# Adafruit_BNO055_and_BMP280_BFF.net
KiCad netlist of a schematic drawn in EAGLE
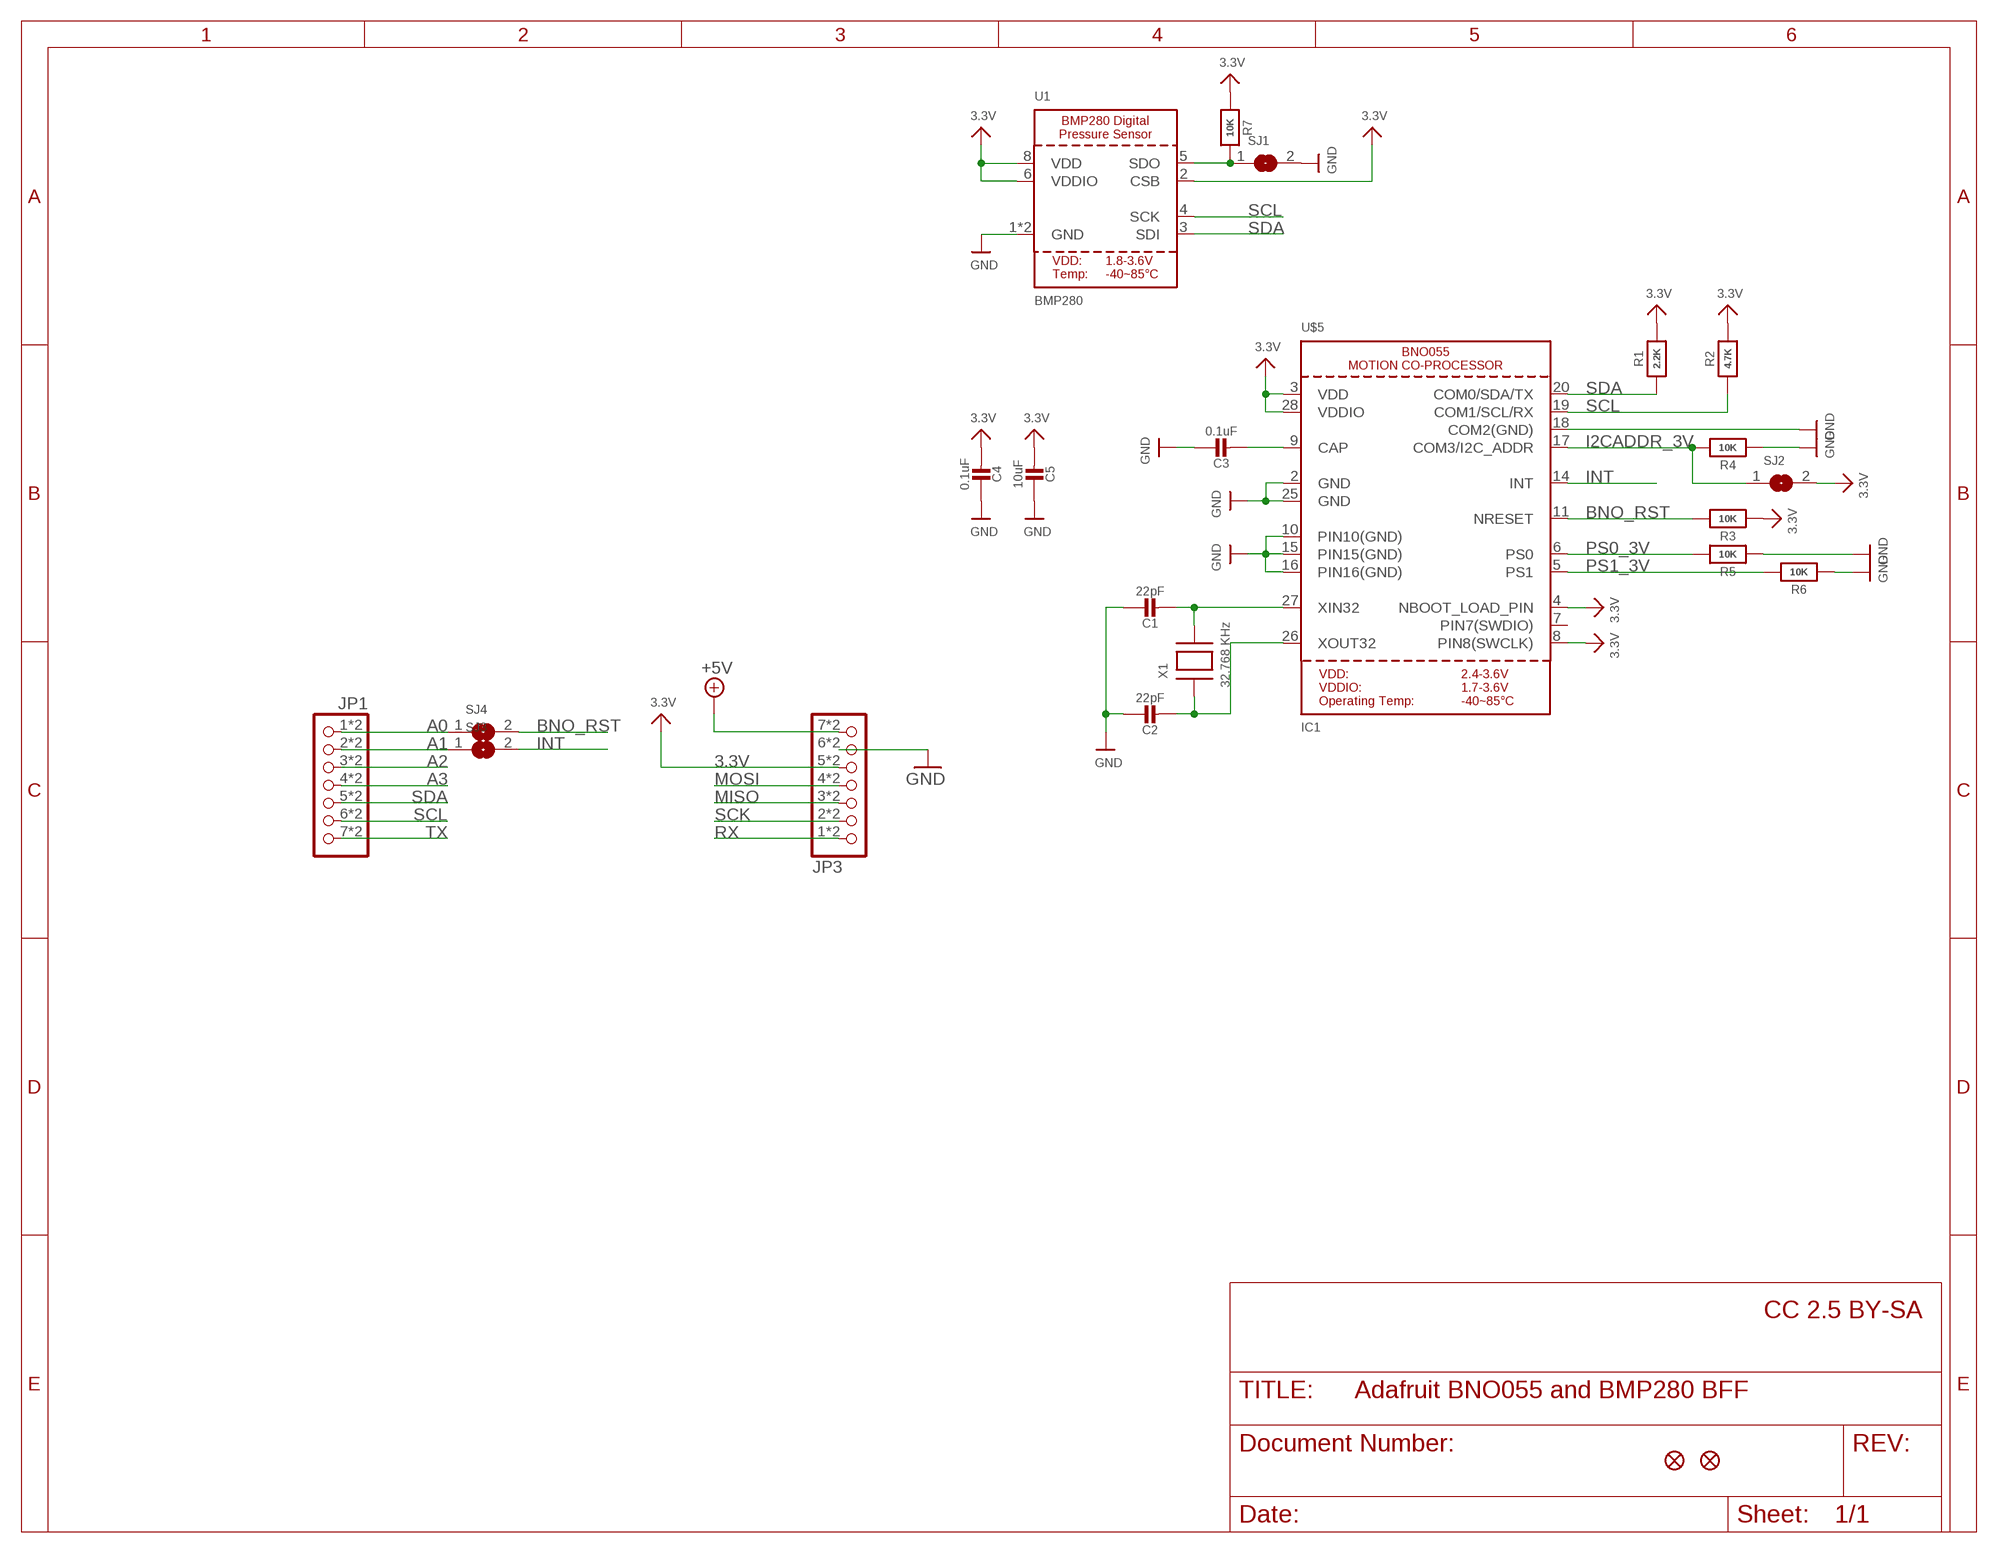
[diagram p0: schematic, sheet 1]

(export (version "E")
  (design (tool "Eeschema 10.0.6"))
  (components
    (comp (ref "C1")
      (value "22pF")
      (footprint "eagle-import:0603-NO")
      (libsource (lib "eagle-import") (part "CAP_CERAMIC0603_NO"))
    )
    (comp (ref "C2")
      (value "22pF")
      (footprint "eagle-import:0603-NO")
      (libsource (lib "eagle-import") (part "CAP_CERAMIC0603_NO"))
    )
    (comp (ref "C3")
      (value "0.1uF")
      (footprint "eagle-import:0603-NO")
      (libsource (lib "eagle-import") (part "CAP_CERAMIC0603_NO"))
    )
    (comp (ref "C4")
      (value "0.1uF")
      (footprint "eagle-import:0603-NO")
      (libsource (lib "eagle-import") (part "CAP_CERAMIC0603_NO"))
    )
    (comp (ref "C5")
      (value "10uF")
      (footprint "eagle-import:0805-NO")
      (libsource (lib "eagle-import") (part "CAP_CERAMIC0805-NOOUTLINE"))
    )
    (comp (ref "JP1")
      (value "HEADER-1X7_CASTEL")
      (footprint "eagle-import:1X07_CASTEL")
      (libsource (lib "eagle-import") (part "HEADER-1X7_CASTEL"))
    )
    (comp (ref "JP3")
      (value "HEADER-1X7_CASTEL")
      (footprint "eagle-import:1X07_CASTEL")
      (libsource (lib "eagle-import") (part "HEADER-1X7_CASTEL"))
    )
    (comp (ref "R1")
      (value "2.2K")
      (footprint "eagle-import:0603-NO")
      (libsource (lib "eagle-import") (part "RESISTOR_0603_NOOUT"))
    )
    (comp (ref "R2")
      (value "4.7K")
      (footprint "eagle-import:0603-NO")
      (libsource (lib "eagle-import") (part "RESISTOR_0603_NOOUT"))
    )
    (comp (ref "R3")
      (value "10K")
      (footprint "eagle-import:0603-NO")
      (libsource (lib "eagle-import") (part "RESISTOR_0603_NOOUT"))
    )
    (comp (ref "R4")
      (value "10K")
      (footprint "eagle-import:0603-NO")
      (libsource (lib "eagle-import") (part "RESISTOR_0603_NOOUT"))
    )
    (comp (ref "R5")
      (value "10K")
      (footprint "eagle-import:0603-NO")
      (libsource (lib "eagle-import") (part "RESISTOR_0603_NOOUT"))
    )
    (comp (ref "R6")
      (value "10K")
      (footprint "eagle-import:0603-NO")
      (libsource (lib "eagle-import") (part "RESISTOR_0603_NOOUT"))
    )
    (comp (ref "R7")
      (value "10K")
      (footprint "eagle-import:0603-NO")
      (libsource (lib "eagle-import") (part "RESISTOR_0603_NOOUT"))
    )
    (comp (ref "SJ1")
      (value "SOLDERJUMPER")
      (footprint "eagle-import:SOLDERJUMPER_ARROW_NOPASTE")
      (libsource (lib "eagle-import") (part "SOLDERJUMPER"))
    )
    (comp (ref "SJ2")
      (value "SOLDERJUMPER")
      (footprint "eagle-import:SOLDERJUMPER_ARROW_NOPASTE")
      (libsource (lib "eagle-import") (part "SOLDERJUMPER"))
    )
    (comp (ref "SJ3")
      (value "SOLDERJUMPER")
      (footprint "eagle-import:SOLDERJUMPER_ARROW_NOPASTE")
      (libsource (lib "eagle-import") (part "SOLDERJUMPER"))
    )
    (comp (ref "SJ4")
      (value "SOLDERJUMPER")
      (footprint "eagle-import:SOLDERJUMPER_ARROW_NOPASTE")
      (libsource (lib "eagle-import") (part "SOLDERJUMPER"))
    )
    (comp (ref "U$5")
      (value "IC1")
      (footprint "eagle-import:BNO055")
      (libsource (lib "eagle-import") (part "BNO055"))
    )
    (comp (ref "U$6")
      (value "FIDUCIAL_0.5MM")
      (footprint "eagle-import:FIDUCIAL_0.5MM")
      (libsource (lib "eagle-import") (part "FIDUCIAL_0.5MM"))
    )
    (comp (ref "U$8")
      (value "FIDUCIAL_0.5MM")
      (footprint "eagle-import:FIDUCIAL_0.5MM")
      (libsource (lib "eagle-import") (part "FIDUCIAL_0.5MM"))
    )
    (comp (ref "U1")
      (value "BMP280")
      (footprint "eagle-import:BMP280")
      (libsource (lib "eagle-import") (part "BMP280"))
    )
    (comp (ref "X1")
      (value "32.768 KHz")
      (footprint "eagle-import:XTAL3215")
      (libsource (lib "eagle-import") (part "XTAL-3.2X1.5"))
    )
  )
  (nets
    (net (code "1") (name "+5V") (class "Default")
      (node (ref "JP3") (pin "7") (pinfunction "7_7") (pintype "passive"))
      (node (ref "JP3") (pin "7C") (pinfunction "7_7C") (pintype "passive"))
    )
    (net (code "2") (name "/A0") (class "Default")
      (node (ref "JP1") (pin "1") (pinfunction "1_1") (pintype "passive"))
      (node (ref "JP1") (pin "1C") (pinfunction "1_1C") (pintype "passive"))
      (node (ref "SJ4") (pin "1") (pinfunction "1_1") (pintype "passive"))
    )
    (net (code "3") (name "/A1") (class "Default")
      (node (ref "JP1") (pin "2") (pinfunction "2_2") (pintype "passive"))
      (node (ref "JP1") (pin "2C") (pinfunction "2_2C") (pintype "passive"))
      (node (ref "SJ3") (pin "1") (pinfunction "1_1") (pintype "passive"))
    )
    (net (code "4") (name "/A2") (class "Default")
      (node (ref "JP1") (pin "3") (pinfunction "3_3") (pintype "passive"))
      (node (ref "JP1") (pin "3C") (pinfunction "3_3C") (pintype "passive"))
    )
    (net (code "5") (name "/A3") (class "Default")
      (node (ref "JP1") (pin "4") (pinfunction "4_4") (pintype "passive"))
      (node (ref "JP1") (pin "4C") (pinfunction "4_4C") (pintype "passive"))
    )
    (net (code "6") (name "/BNO_RST") (class "Default")
      (node (ref "R3") (pin "2") (pinfunction "2_2") (pintype "passive"))
      (node (ref "SJ4") (pin "2") (pinfunction "2_2") (pintype "passive"))
      (node (ref "U$5") (pin "11") (pinfunction "NRESET_11") (pintype "bidirectional"))
    )
    (net (code "7") (name "/I2CADDR_3V") (class "Default")
      (node (ref "R4") (pin "2") (pinfunction "2_2") (pintype "passive"))
      (node (ref "SJ2") (pin "1") (pinfunction "1_1") (pintype "passive"))
      (node (ref "U$5") (pin "17") (pinfunction "COM3/I2C_ADDR_17") (pintype "bidirectional"))
    )
    (net (code "8") (name "/INT") (class "Default")
      (node (ref "SJ3") (pin "2") (pinfunction "2_2") (pintype "passive"))
      (node (ref "U$5") (pin "14") (pinfunction "INT_14") (pintype "output"))
    )
    (net (code "9") (name "/MISO") (class "Default")
      (node (ref "JP3") (pin "3") (pinfunction "3_3") (pintype "passive"))
      (node (ref "JP3") (pin "3C") (pinfunction "3_3C") (pintype "passive"))
    )
    (net (code "10") (name "/MOSI") (class "Default")
      (node (ref "JP3") (pin "4") (pinfunction "4_4") (pintype "passive"))
      (node (ref "JP3") (pin "4C") (pinfunction "4_4C") (pintype "passive"))
    )
    (net (code "11") (name "/PS0_3V") (class "Default")
      (node (ref "R5") (pin "2") (pinfunction "2_2") (pintype "passive"))
      (node (ref "U$5") (pin "6") (pinfunction "PS0_6") (pintype "input"))
    )
    (net (code "12") (name "/PS1_3V") (class "Default")
      (node (ref "R6") (pin "2") (pinfunction "2_2") (pintype "passive"))
      (node (ref "U$5") (pin "5") (pinfunction "PS1_5") (pintype "input"))
    )
    (net (code "13") (name "/RX") (class "Default")
      (node (ref "JP3") (pin "1") (pinfunction "1_1") (pintype "passive"))
      (node (ref "JP3") (pin "1C") (pinfunction "1_1C") (pintype "passive"))
    )
    (net (code "14") (name "/SCK") (class "Default")
      (node (ref "JP3") (pin "2") (pinfunction "2_2") (pintype "passive"))
      (node (ref "JP3") (pin "2C") (pinfunction "2_2C") (pintype "passive"))
    )
    (net (code "15") (name "/SCL") (class "Default")
      (node (ref "JP1") (pin "6") (pinfunction "6_6") (pintype "passive"))
      (node (ref "JP1") (pin "6C") (pinfunction "6_6C") (pintype "passive"))
      (node (ref "R2") (pin "1") (pinfunction "1_1") (pintype "passive"))
      (node (ref "U$5") (pin "19") (pinfunction "COM1/SCL/RX_19") (pintype "bidirectional"))
      (node (ref "U1") (pin "4") (pinfunction "SCK_4") (pintype "input"))
    )
    (net (code "16") (name "/SDA") (class "Default")
      (node (ref "JP1") (pin "5") (pinfunction "5_5") (pintype "passive"))
      (node (ref "JP1") (pin "5C") (pinfunction "5_5C") (pintype "passive"))
      (node (ref "R1") (pin "1") (pinfunction "1_1") (pintype "passive"))
      (node (ref "U$5") (pin "20") (pinfunction "COM0/SDA/TX_20") (pintype "bidirectional"))
      (node (ref "U1") (pin "3") (pinfunction "SDI_3") (pintype "input"))
    )
    (net (code "17") (name "/TX") (class "Default")
      (node (ref "JP1") (pin "7") (pinfunction "7_7") (pintype "passive"))
      (node (ref "JP1") (pin "7C") (pinfunction "7_7C") (pintype "passive"))
    )
    (net (code "18") (name "3.3V") (class "Default")
      (node (ref "C4") (pin "2") (pinfunction "2_2") (pintype "passive"))
      (node (ref "C5") (pin "2") (pinfunction "2_2") (pintype "passive"))
      (node (ref "JP3") (pin "5") (pinfunction "5_5") (pintype "passive"))
      (node (ref "JP3") (pin "5C") (pinfunction "5_5C") (pintype "passive"))
      (node (ref "R1") (pin "2") (pinfunction "2_2") (pintype "passive"))
      (node (ref "R2") (pin "2") (pinfunction "2_2") (pintype "passive"))
      (node (ref "R3") (pin "1") (pinfunction "1_1") (pintype "passive"))
      (node (ref "R7") (pin "1") (pinfunction "1_1") (pintype "passive"))
      (node (ref "SJ2") (pin "2") (pinfunction "2_2") (pintype "passive"))
      (node (ref "U$5") (pin "28") (pinfunction "VDDIO_28") (pintype "power_in"))
      (node (ref "U$5") (pin "3") (pinfunction "VDD_3") (pintype "power_in"))
      (node (ref "U$5") (pin "4") (pinfunction "NBOOT_LOAD_PIN_4") (pintype "bidirectional"))
      (node (ref "U$5") (pin "8") (pinfunction "PIN8(SWCLK)_8") (pintype "bidirectional"))
      (node (ref "U1") (pin "2") (pinfunction "CSB_2") (pintype "input"))
      (node (ref "U1") (pin "6") (pinfunction "VDDIO_6") (pintype "power_in"))
      (node (ref "U1") (pin "8") (pinfunction "VDD_8") (pintype "power_in"))
    )
    (net (code "19") (name "GND") (class "Default")
      (node (ref "C1") (pin "1") (pinfunction "1_1") (pintype "passive"))
      (node (ref "C2") (pin "1") (pinfunction "1_1") (pintype "passive"))
      (node (ref "C3") (pin "1") (pinfunction "1_1") (pintype "passive"))
      (node (ref "C4") (pin "1") (pinfunction "1_1") (pintype "passive"))
      (node (ref "C5") (pin "1") (pinfunction "1_1") (pintype "passive"))
      (node (ref "JP3") (pin "6") (pinfunction "6_6") (pintype "passive"))
      (node (ref "JP3") (pin "6C") (pinfunction "6_6C") (pintype "passive"))
      (node (ref "R4") (pin "1") (pinfunction "1_1") (pintype "passive"))
      (node (ref "R5") (pin "1") (pinfunction "1_1") (pintype "passive"))
      (node (ref "R6") (pin "1") (pinfunction "1_1") (pintype "passive"))
      (node (ref "SJ1") (pin "2") (pinfunction "2_2") (pintype "passive"))
      (node (ref "U$5") (pin "10") (pinfunction "PIN10(GND)_10") (pintype "bidirectional"))
      (node (ref "U$5") (pin "15") (pinfunction "PIN15(GND)_15") (pintype "bidirectional"))
      (node (ref "U$5") (pin "16") (pinfunction "PIN16(GND)_16") (pintype "bidirectional"))
      (node (ref "U$5") (pin "18") (pinfunction "COM2(GND)_18") (pintype "bidirectional"))
      (node (ref "U$5") (pin "2") (pinfunction "GND_2") (pintype "power_in"))
      (node (ref "U$5") (pin "25") (pinfunction "GND_25") (pintype "power_in"))
      (node (ref "U1") (pin "1") (pinfunction "GND_1") (pintype "power_in"))
      (node (ref "U1") (pin "7") (pinfunction "GND_7") (pintype "power_in"))
    )
    (net (code "20") (name "Net-(U$5-CAP)") (class "Default")
      (node (ref "C3") (pin "2") (pinfunction "2_2") (pintype "passive"))
      (node (ref "U$5") (pin "9") (pinfunction "CAP_9") (pintype "passive"))
    )
    (net (code "21") (name "Net-(U$5-XIN32)") (class "Default")
      (node (ref "C1") (pin "2") (pinfunction "2_2") (pintype "passive"))
      (node (ref "U$5") (pin "27") (pinfunction "XIN32_27") (pintype "input"))
      (node (ref "X1") (pin "P$2") (pinfunction "P$2_P$2") (pintype "bidirectional"))
    )
    (net (code "22") (name "Net-(U$5-XOUT32)") (class "Default")
      (node (ref "C2") (pin "2") (pinfunction "2_2") (pintype "passive"))
      (node (ref "U$5") (pin "26") (pinfunction "XOUT32_26") (pintype "output"))
      (node (ref "X1") (pin "P$1") (pinfunction "P$1_P$1") (pintype "bidirectional"))
    )
    (net (code "23") (name "Net-(U1-SDO)") (class "Default")
      (node (ref "R7") (pin "2") (pinfunction "2_2") (pintype "passive"))
      (node (ref "SJ1") (pin "1") (pinfunction "1_1") (pintype "passive"))
      (node (ref "U1") (pin "5") (pinfunction "SDO_5") (pintype "output"))
    )
    (net (code "24") (name "unconnected-(U$5-PIN7(SWDIO)-Pad7)") (class "Default")
      (node (ref "U$5") (pin "7") (pinfunction "PIN7(SWDIO)_7") (pintype "bidirectional"))
    )
  )
)
